# layout.net
KiCad netlist of a schematic drawn in Altium Designer
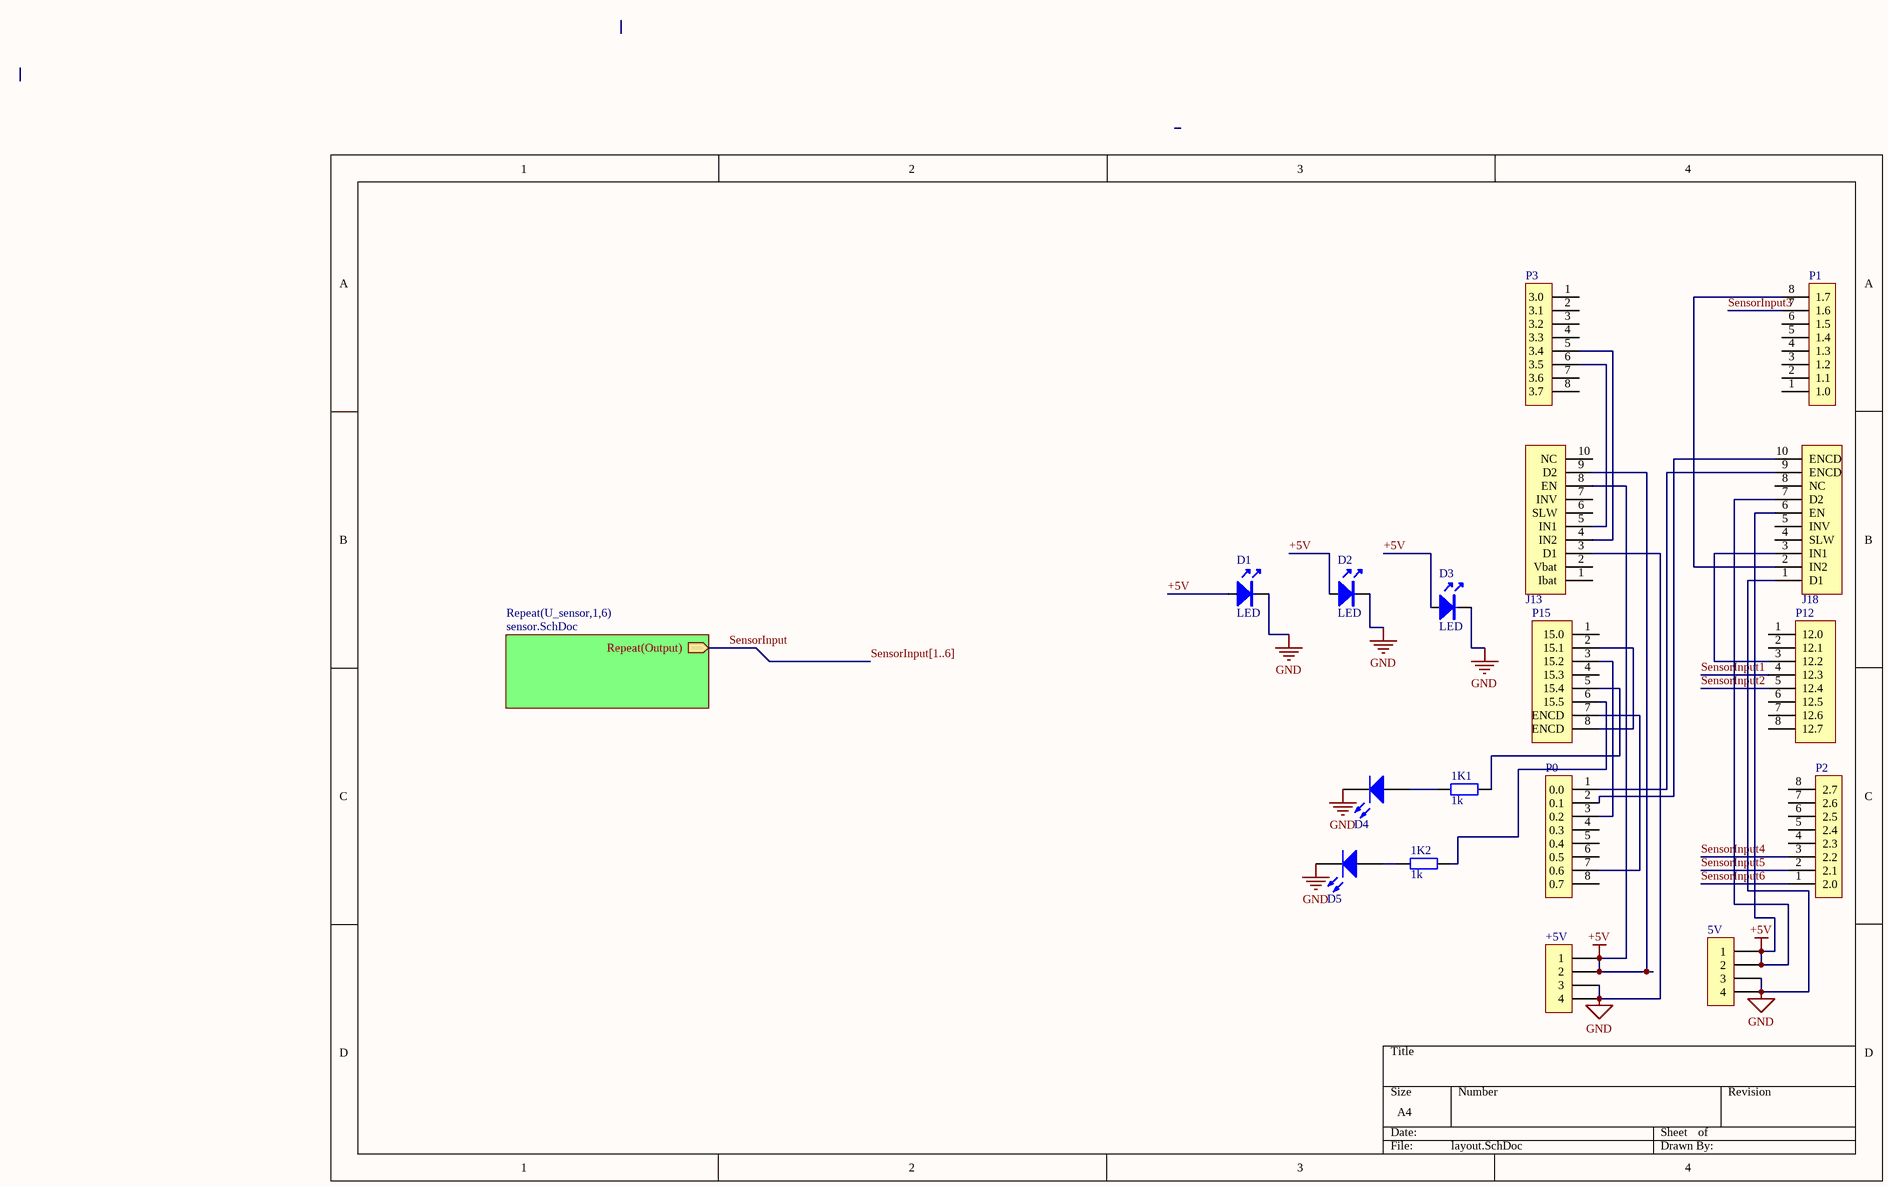
[diagram p0: layout.SchDoc]

(export (version "E")
  (design (tool "Eeschema 10.0.6"))
  (components
    (comp (ref "+5V")
      (value "5V")
      (footprint "IDC4")
      (description "Connector")
      (libsource (lib "Miscellaneous Devices") (part "CON4"))
    )
    (comp (ref "1K1")
      (value "1k")
      (footprint "0805 RES")
      (description "0805 resistor")
      (fields (field (name "PUBLISHER") "Altium Limited"))
      (libsource (lib "EE209_Library") (part "Res_SMT_0805"))
    )
    (comp (ref "1K2")
      (value "1k")
      (footprint "0805 RES")
      (description "0805 resistor")
      (fields (field (name "PUBLISHER") "Altium Limited"))
      (libsource (lib "EE209_Library") (part "Res_SMT_0805"))
    )
    (comp (ref "5V")
      (value "5V")
      (footprint "IDC4")
      (description "Connector")
      (libsource (lib "Miscellaneous Devices") (part "CON4"))
    )
    (comp (ref "D1") (value "LED") (footprint "LED0.1/5MM") (libsource (lib "COMSYS301_2013") (part "LED")))
    (comp (ref "D2") (value "LED") (footprint "LED0.1/5MM") (libsource (lib "COMSYS301_2013") (part "LED")))
    (comp (ref "D3") (value "LED") (footprint "LED0.1/5MM") (libsource (lib "COMSYS301_2013") (part "LED")))
    (comp (ref "D4")
      (value "LTST-C170KGKT")
      (footprint "0805 LED")
      (description "SMT LED 0805 size")
      (fields (field (name "MANUFACTURER") "Lite-On Inc."))
      (libsource (lib "EE209_Library") (part "LED_SMT_0805"))
    )
    (comp (ref "D5")
      (value "LTST-C170KGKT")
      (footprint "0805 LED")
      (description "SMT LED 0805 size")
      (fields (field (name "MANUFACTURER") "Lite-On Inc."))
      (libsource (lib "EE209_Library") (part "LED_SMT_0805"))
    )
    (comp (ref "J13")
      (value "CON10")
      (footprint "idc10")
      (description "Connector")
      (libsource (lib "Miscellaneous Devices") (part "CON10"))
    )
    (comp (ref "J18")
      (value "CON10")
      (footprint "IDC10")
      (description "Connector")
      (libsource (lib "") (part "CON10_1"))
    )
    (comp (ref "P0")
      (value "P0")
      (footprint "idc8")
      (description "Connector")
      (libsource (lib "") (part "CON8_1"))
    )
    (comp (ref "P1")
      (value "P1")
      (footprint "idc8")
      (description "Connector")
      (libsource (lib "Miscellaneous Devices") (part "CON8"))
    )
    (comp (ref "P2")
      (value "P2")
      (footprint "idc8")
      (description "Connector")
      (libsource (lib "") (part "CON8_2"))
    )
    (comp (ref "P3")
      (value "P3")
      (footprint "idc8")
      (description "Connector")
      (libsource (lib "") (part "CON8_1"))
    )
    (comp (ref "P12")
      (value "P12")
      (footprint "idc8")
      (description "Connector")
      (libsource (lib "Miscellaneous Devices") (part "CON8_1"))
    )
    (comp (ref "P15")
      (value "P15")
      (footprint "idc8")
      (description "Connector")
      (libsource (lib "") (part "CON8_1_1"))
    )
  )
  (nets
    (net (code "1") (name "+5V") (class "Default")
      (node (ref "+5V") (pin "1") (pinfunction "1_1") (pintype "passive"))
      (node (ref "+5V") (pin "2") (pinfunction "2_2") (pintype "passive"))
      (node (ref "5V") (pin "1") (pinfunction "1_1") (pintype "passive"))
      (node (ref "5V") (pin "2") (pinfunction "2_2") (pintype "passive"))
      (node (ref "D1") (pin "A") (pinfunction "1_A") (pintype "passive"))
      (node (ref "D2") (pin "A") (pinfunction "1_A") (pintype "passive"))
      (node (ref "D3") (pin "A") (pinfunction "1_A") (pintype "passive"))
      (node (ref "J13") (pin "8") (pinfunction "EN_8") (pintype "passive"))
      (node (ref "J13") (pin "9") (pinfunction "D2_9") (pintype "passive"))
      (node (ref "J18") (pin "6") (pinfunction "EN_6") (pintype "passive"))
      (node (ref "J18") (pin "7") (pinfunction "D2_7") (pintype "passive"))
    )
    (net (code "3") (name "/SensorInput1") (class "Default")
      (node (ref "P12") (pin "4") (pinfunction "12.3_4") (pintype "passive"))
    )
    (net (code "4") (name "/SensorInput2") (class "Default")
      (node (ref "P12") (pin "5") (pinfunction "12.4_5") (pintype "passive"))
    )
    (net (code "5") (name "/SensorInput3") (class "Default")
      (node (ref "P1") (pin "7") (pinfunction "1.6_7") (pintype "passive"))
    )
    (net (code "6") (name "/SensorInput4") (class "Default")
      (node (ref "P2") (pin "3") (pinfunction "2.2_3") (pintype "passive"))
    )
    (net (code "7") (name "/SensorInput5") (class "Default")
      (node (ref "P2") (pin "2") (pinfunction "2.1_2") (pintype "passive"))
    )
    (net (code "8") (name "/SensorInput6") (class "Default")
      (node (ref "P2") (pin "1") (pinfunction "2.0_1") (pintype "passive"))
    )
    (net (code "10") (name "GND") (class "Default")
      (node (ref "+5V") (pin "3") (pinfunction "3_3") (pintype "passive"))
      (node (ref "+5V") (pin "4") (pinfunction "4_4") (pintype "passive"))
      (node (ref "5V") (pin "3") (pinfunction "3_3") (pintype "passive"))
      (node (ref "5V") (pin "4") (pinfunction "4_4") (pintype "passive"))
      (node (ref "D1") (pin "K") (pinfunction "2_K") (pintype "passive"))
      (node (ref "D2") (pin "K") (pinfunction "2_K") (pintype "passive"))
      (node (ref "D3") (pin "K") (pinfunction "2_K") (pintype "passive"))
      (node (ref "D4") (pin "2") (pinfunction "K_2") (pintype "passive"))
      (node (ref "D5") (pin "2") (pinfunction "K_2") (pintype "passive"))
      (node (ref "J13") (pin "3") (pinfunction "D1_3") (pintype "passive"))
      (node (ref "J18") (pin "1") (pinfunction "D1_1") (pintype "passive"))
    )
    (net (code "11") (name "Net-(D4-A)") (class "Default")
      (node (ref "1K1") (pin "1") (pinfunction "1_1") (pintype "passive"))
      (node (ref "D4") (pin "1") (pinfunction "A_1") (pintype "passive"))
    )
    (net (code "12") (name "Net-(D5-A)") (class "Default")
      (node (ref "1K2") (pin "1") (pinfunction "1_1") (pintype "passive"))
      (node (ref "D5") (pin "1") (pinfunction "A_1") (pintype "passive"))
    )
    (net (code "13") (name "Net-(J13-IN1)") (class "Default")
      (node (ref "J13") (pin "5") (pinfunction "IN1_5") (pintype "passive"))
      (node (ref "P3") (pin "6") (pinfunction "3.5_6") (pintype "passive"))
    )
    (net (code "14") (name "Net-(J13-IN2)") (class "Default")
      (node (ref "J13") (pin "4") (pinfunction "IN2_4") (pintype "passive"))
      (node (ref "P3") (pin "5") (pinfunction "3.4_5") (pintype "passive"))
    )
    (net (code "15") (name "Net-(J18-IN1)") (class "Default")
      (node (ref "J18") (pin "3") (pinfunction "IN1_3") (pintype "passive"))
      (node (ref "P12") (pin "3") (pinfunction "12.2_3") (pintype "passive"))
    )
    (net (code "16") (name "Net-(J18-IN2)") (class "Default")
      (node (ref "J18") (pin "2") (pinfunction "IN2_2") (pintype "passive"))
      (node (ref "P1") (pin "8") (pinfunction "1.7_8") (pintype "passive"))
    )
    (net (code "17") (name "Net-(P0-3.0)") (class "Default")
      (node (ref "J18") (pin "9") (pinfunction "ENCD_9") (pintype "passive"))
      (node (ref "P0") (pin "1") (pinfunction "3.0_1") (pintype "passive"))
    )
    (net (code "18") (name "Net-(P0-3.1)") (class "Default")
      (node (ref "J18") (pin "10") (pinfunction "ENCD_10") (pintype "passive"))
      (node (ref "P0") (pin "2") (pinfunction "3.1_2") (pintype "passive"))
    )
    (net (code "19") (name "Net-(P0-3.2)") (class "Default")
      (node (ref "P0") (pin "3") (pinfunction "3.2_3") (pintype "passive"))
      (node (ref "P15") (pin "3") (pinfunction "15.2_3") (pintype "passive"))
    )
    (net (code "20") (name "Net-(P0-3.6)") (class "Default")
      (node (ref "P0") (pin "7") (pinfunction "3.6_7") (pintype "passive"))
      (node (ref "P15") (pin "7") (pinfunction "ENCD_7") (pintype "passive"))
    )
    (net (code "21") (name "Net-(P15-15.1)") (class "Default")
      (node (ref "P15") (pin "2") (pinfunction "15.1_2") (pintype "passive"))
      (node (ref "P15") (pin "8") (pinfunction "ENCD_8") (pintype "passive"))
    )
    (net (code "22") (name "Net-(P15-15.4)") (class "Default")
      (node (ref "1K1") (pin "2") (pinfunction "2_2") (pintype "passive"))
      (node (ref "P15") (pin "5") (pinfunction "15.4_5") (pintype "passive"))
    )
    (net (code "23") (name "Net-(P15-15.5)") (class "Default")
      (node (ref "1K2") (pin "2") (pinfunction "2_2") (pintype "passive"))
      (node (ref "P15") (pin "6") (pinfunction "15.5_6") (pintype "passive"))
    )
    (net (code "24") (name "unconnected-(J13-INV-Pad7)") (class "Default")
      (node (ref "J13") (pin "7") (pinfunction "INV_7") (pintype "passive"))
    )
    (net (code "25") (name "unconnected-(J13-Ibat-Pad1)") (class "Default")
      (node (ref "J13") (pin "1") (pinfunction "Ibat_1") (pintype "passive"))
    )
    (net (code "26") (name "unconnected-(J13-NC-Pad10)") (class "Default")
      (node (ref "J13") (pin "10") (pinfunction "NC_10") (pintype "passive"))
    )
    (net (code "27") (name "unconnected-(J13-SLW-Pad6)") (class "Default")
      (node (ref "J13") (pin "6") (pinfunction "SLW_6") (pintype "passive"))
    )
    (net (code "28") (name "unconnected-(J13-Vbat-Pad2)") (class "Default")
      (node (ref "J13") (pin "2") (pinfunction "Vbat_2") (pintype "passive"))
    )
    (net (code "29") (name "unconnected-(J18-INV-Pad5)") (class "Default")
      (node (ref "J18") (pin "5") (pinfunction "INV_5") (pintype "passive"))
    )
    (net (code "30") (name "unconnected-(J18-NC-Pad8)") (class "Default")
      (node (ref "J18") (pin "8") (pinfunction "NC_8") (pintype "passive"))
    )
    (net (code "31") (name "unconnected-(J18-SLW-Pad4)") (class "Default")
      (node (ref "J18") (pin "4") (pinfunction "SLW_4") (pintype "passive"))
    )
    (net (code "32") (name "unconnected-(P0-3.3-Pad4)") (class "Default")
      (node (ref "P0") (pin "4") (pinfunction "3.3_4") (pintype "passive"))
    )
    (net (code "33") (name "unconnected-(P0-3.4-Pad5)") (class "Default")
      (node (ref "P0") (pin "5") (pinfunction "3.4_5") (pintype "passive"))
    )
    (net (code "34") (name "unconnected-(P0-3.5-Pad6)") (class "Default")
      (node (ref "P0") (pin "6") (pinfunction "3.5_6") (pintype "passive"))
    )
    (net (code "35") (name "unconnected-(P0-3.7-Pad8)") (class "Default")
      (node (ref "P0") (pin "8") (pinfunction "3.7_8") (pintype "passive"))
    )
    (net (code "36") (name "unconnected-(P1-1.0-Pad1)") (class "Default")
      (node (ref "P1") (pin "1") (pinfunction "1.0_1") (pintype "passive"))
    )
    (net (code "37") (name "unconnected-(P1-1.1-Pad2)") (class "Default")
      (node (ref "P1") (pin "2") (pinfunction "1.1_2") (pintype "passive"))
    )
    (net (code "38") (name "unconnected-(P1-1.2-Pad3)") (class "Default")
      (node (ref "P1") (pin "3") (pinfunction "1.2_3") (pintype "passive"))
    )
    (net (code "39") (name "unconnected-(P1-1.3-Pad4)") (class "Default")
      (node (ref "P1") (pin "4") (pinfunction "1.3_4") (pintype "passive"))
    )
    (net (code "40") (name "unconnected-(P1-1.4-Pad5)") (class "Default")
      (node (ref "P1") (pin "5") (pinfunction "1.4_5") (pintype "passive"))
    )
    (net (code "41") (name "unconnected-(P1-1.5-Pad6)") (class "Default")
      (node (ref "P1") (pin "6") (pinfunction "1.5_6") (pintype "passive"))
    )
    (net (code "42") (name "unconnected-(P2-2.3-Pad4)") (class "Default")
      (node (ref "P2") (pin "4") (pinfunction "2.3_4") (pintype "passive"))
    )
    (net (code "43") (name "unconnected-(P2-2.4-Pad5)") (class "Default")
      (node (ref "P2") (pin "5") (pinfunction "2.4_5") (pintype "passive"))
    )
    (net (code "44") (name "unconnected-(P2-2.5-Pad6)") (class "Default")
      (node (ref "P2") (pin "6") (pinfunction "2.5_6") (pintype "passive"))
    )
    (net (code "45") (name "unconnected-(P2-2.6-Pad7)") (class "Default")
      (node (ref "P2") (pin "7") (pinfunction "2.6_7") (pintype "passive"))
    )
    (net (code "46") (name "unconnected-(P2-2.7-Pad8)") (class "Default")
      (node (ref "P2") (pin "8") (pinfunction "2.7_8") (pintype "passive"))
    )
    (net (code "47") (name "unconnected-(P3-3.0-Pad1)") (class "Default")
      (node (ref "P3") (pin "1") (pinfunction "3.0_1") (pintype "passive"))
    )
    (net (code "48") (name "unconnected-(P3-3.1-Pad2)") (class "Default")
      (node (ref "P3") (pin "2") (pinfunction "3.1_2") (pintype "passive"))
    )
    (net (code "49") (name "unconnected-(P3-3.2-Pad3)") (class "Default")
      (node (ref "P3") (pin "3") (pinfunction "3.2_3") (pintype "passive"))
    )
    (net (code "50") (name "unconnected-(P3-3.3-Pad4)") (class "Default")
      (node (ref "P3") (pin "4") (pinfunction "3.3_4") (pintype "passive"))
    )
    (net (code "51") (name "unconnected-(P3-3.6-Pad7)") (class "Default")
      (node (ref "P3") (pin "7") (pinfunction "3.6_7") (pintype "passive"))
    )
    (net (code "52") (name "unconnected-(P3-3.7-Pad8)") (class "Default")
      (node (ref "P3") (pin "8") (pinfunction "3.7_8") (pintype "passive"))
    )
    (net (code "53") (name "unconnected-(P12-12.0-Pad1)") (class "Default")
      (node (ref "P12") (pin "1") (pinfunction "12.0_1") (pintype "passive"))
    )
    (net (code "54") (name "unconnected-(P12-12.1-Pad2)") (class "Default")
      (node (ref "P12") (pin "2") (pinfunction "12.1_2") (pintype "passive"))
    )
    (net (code "55") (name "unconnected-(P12-12.5-Pad6)") (class "Default")
      (node (ref "P12") (pin "6") (pinfunction "12.5_6") (pintype "passive"))
    )
    (net (code "56") (name "unconnected-(P12-12.6-Pad7)") (class "Default")
      (node (ref "P12") (pin "7") (pinfunction "12.6_7") (pintype "passive"))
    )
    (net (code "57") (name "unconnected-(P12-12.7-Pad8)") (class "Default")
      (node (ref "P12") (pin "8") (pinfunction "12.7_8") (pintype "passive"))
    )
    (net (code "58") (name "unconnected-(P15-15.0-Pad1)") (class "Default")
      (node (ref "P15") (pin "1") (pinfunction "15.0_1") (pintype "passive"))
    )
    (net (code "59") (name "unconnected-(P15-15.3-Pad4)") (class "Default")
      (node (ref "P15") (pin "4") (pinfunction "15.3_4") (pintype "passive"))
    )
  )
)
